# LDK320ADU50R_5V0_LDO_breakout.net
KiCad netlist of a schematic drawn in EAGLE
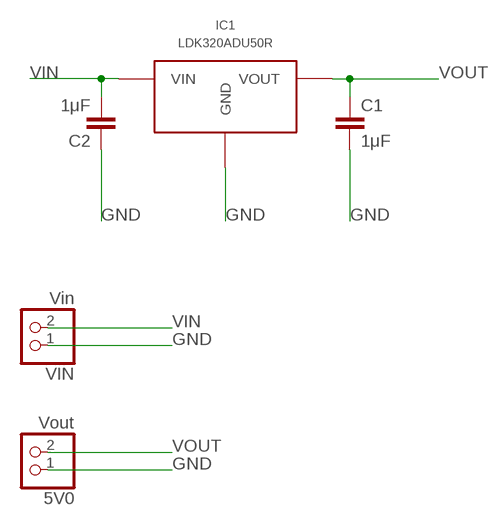
[diagram p0: schematic, sheet 1]

(export (version "E")
  (design (tool "Eeschema 10.0.6"))
  (components
    (comp (ref "5V0")
      (value "Vout")
      (footprint "eagle-import:1X02")
      (libsource (lib "eagle-import") (part "PINHD-1X2"))
    )
    (comp (ref "C1")
      (value "1μF")
      (footprint "eagle-import:C0402")
      (libsource (lib "eagle-import") (part "C-EUC0402"))
    )
    (comp (ref "C2")
      (value "1μF")
      (footprint "eagle-import:C0402")
      (libsource (lib "eagle-import") (part "C-EUC0402"))
    )
    (comp (ref "IC1")
      (value "LDK320ADU50R")
      (footprint "eagle-import:SOT-89-D")
      (libsource (lib "eagle-import") (part "LDO"))
    )
    (comp (ref "VIN")
      (value "Vin")
      (footprint "eagle-import:1X02")
      (libsource (lib "eagle-import") (part "PINHD-1X2"))
    )
  )
  (nets
    (net (code "1") (name "/GND") (class "Default")
      (node (ref "5V0") (pin "1") (pinfunction "1_1") (pintype "passive"))
      (node (ref "C1") (pin "2") (pinfunction "2_2") (pintype "passive"))
      (node (ref "C2") (pin "1") (pinfunction "1_1") (pintype "passive"))
      (node (ref "IC1") (pin "GND") (pinfunction "GND_GND") (pintype "bidirectional"))
      (node (ref "VIN") (pin "1") (pinfunction "1_1") (pintype "passive"))
    )
    (net (code "2") (name "/VIN") (class "Default")
      (node (ref "C2") (pin "2") (pinfunction "2_2") (pintype "passive"))
      (node (ref "IC1") (pin "VIN") (pinfunction "VIN_VIN") (pintype "bidirectional"))
      (node (ref "VIN") (pin "2") (pinfunction "2_2") (pintype "passive"))
    )
    (net (code "3") (name "/VOUT") (class "Default")
      (node (ref "5V0") (pin "2") (pinfunction "2_2") (pintype "passive"))
      (node (ref "C1") (pin "1") (pinfunction "1_1") (pintype "passive"))
      (node (ref "IC1") (pin "VOUT") (pinfunction "VOUT_VOUT") (pintype "bidirectional"))
    )
  )
)
